# MCU.net
KiCad netlist of a schematic drawn in Altium Designer
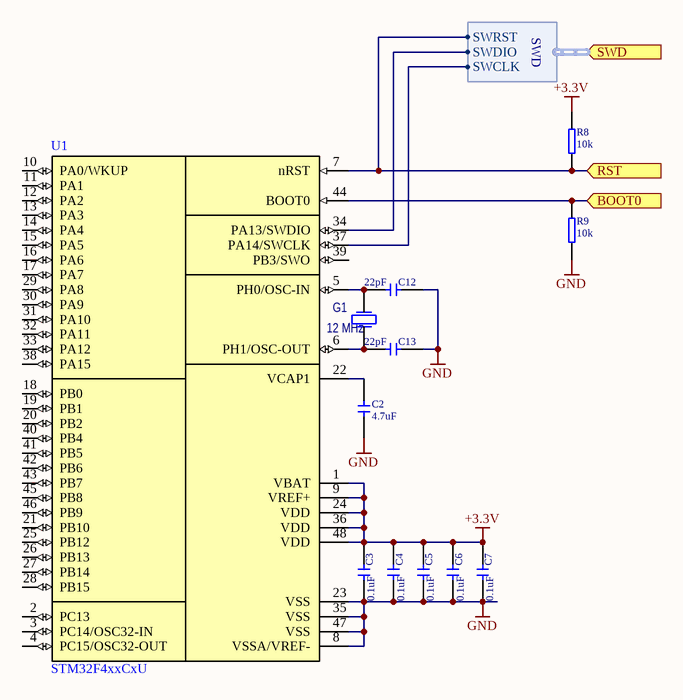
[diagram p0: MCU.SchDoc]

(export (version "E")
  (design (tool "Eeschema 10.0.6"))
  (components
    (comp (ref "C2")
      (value "4.7uF")
      (footprint "CERCAP 0603")
      (description "Capacitor")
      (fields (field (name "Comment") "CERCAP 0603 4.7uF * X7R"))
      (libsource (lib "!main") (part "!Capacitor"))
    )
    (comp (ref "C3")
      (value "0.1uF")
      (footprint "CERCAP 0402")
      (description "Capacitor")
      (fields (field (name "Comment") "CERCAP 0402 0.1uF * X7R"))
      (libsource (lib "!main") (part "!Capacitor"))
    )
    (comp (ref "C4")
      (value "0.1uF")
      (footprint "CERCAP 0402")
      (description "Capacitor")
      (fields (field (name "Comment") "CERCAP 0402 0.1uF * X7R"))
      (libsource (lib "!main") (part "!Capacitor"))
    )
    (comp (ref "C5")
      (value "0.1uF")
      (footprint "CERCAP 0402")
      (description "Capacitor")
      (fields (field (name "Comment") "CERCAP 0402 0.1uF * X7R"))
      (libsource (lib "!main") (part "!Capacitor"))
    )
    (comp (ref "C6")
      (value "0.1uF")
      (footprint "CERCAP 0402")
      (description "Capacitor")
      (fields (field (name "Comment") "CERCAP 0402 0.1uF * X7R"))
      (libsource (lib "!main") (part "!Capacitor"))
    )
    (comp (ref "C7")
      (value "0.1uF")
      (footprint "CERCAP 0402")
      (description "Capacitor")
      (fields (field (name "Comment") "CERCAP 0402 0.1uF * X7R"))
      (libsource (lib "!main") (part "!Capacitor"))
    )
    (comp (ref "C12")
      (value "22pF")
      (footprint "CERCAP 0402")
      (description "Capacitor")
      (fields (field (name "Comment") "CERCAP 0402 22pF * X7R"))
      (libsource (lib "!main") (part "!Capacitor"))
    )
    (comp (ref "C13")
      (value "22pF")
      (footprint "CERCAP 0402")
      (description "Capacitor")
      (fields (field (name "Comment") "CERCAP 0402 22pF * X7R"))
      (libsource (lib "!main") (part "!Capacitor"))
    )
    (comp (ref "G1")
      (value "12 MHz")
      (footprint "3225")
      (description "Crystal")
      (fields (field (name "Comment") "322512 MHz"))
      (libsource (lib "!main") (part "Crystal"))
    )
    (comp (ref "R8")
      (value "10k")
      (footprint "RES 0402")
      (description "Resistor")
      (fields (field (name "Comment") "RES 0402 10k"))
      (libsource (lib "!main") (part "!Resistor"))
    )
    (comp (ref "R9")
      (value "10k")
      (footprint "RES 0402")
      (description "Resistor")
      (fields (field (name "Comment") "RES 0402 10k"))
      (libsource (lib "!main") (part "!Resistor"))
    )
    (comp (ref "U1")
      (value "STM32F4xxCxU")
      (footprint "QFN-48")
      (description "Cortex-M4")
      (libsource (lib "MCU_CPU") (part "STM32F4xxCxU"))
    )
  )
  (nets
    (net (code "2") (name "+3.3V") (class "Default")
      (node (ref "C3") (pin "2") (pintype "passive"))
      (node (ref "C4") (pin "2") (pintype "passive"))
      (node (ref "C5") (pin "2") (pintype "passive"))
      (node (ref "C6") (pin "2") (pintype "passive"))
      (node (ref "C7") (pin "2") (pintype "passive"))
      (node (ref "R8") (pin "2") (pinfunction "12_2") (pintype "passive"))
      (node (ref "U1") (pin "1") (pinfunction "VBAT_1") (pintype "power_in"))
      (node (ref "U1") (pin "24") (pinfunction "VDD_24") (pintype "power_in"))
      (node (ref "U1") (pin "36") (pinfunction "VDD_36") (pintype "power_in"))
      (node (ref "U1") (pin "48") (pinfunction "VDD_48") (pintype "power_in"))
      (node (ref "U1") (pin "9") (pinfunction "VREF+_9") (pintype "power_in"))
    )
    (net (code "3") (name "/BOOT0") (class "Default")
      (node (ref "R9") (pin "2") (pinfunction "12_2") (pintype "passive"))
      (node (ref "U1") (pin "44") (pinfunction "BOOT0_44") (pintype "input"))
    )
    (net (code "4") (name "/RST") (class "Default")
      (node (ref "R8") (pin "1") (pinfunction "11_1") (pintype "passive"))
      (node (ref "U1") (pin "7") (pinfunction "nRST_7") (pintype "input"))
    )
    (net (code "5") (name "/SWCLK") (class "Default")
      (node (ref "U1") (pin "37") (pinfunction "PA14/SWCLK_37") (pintype "bidirectional"))
    )
    (net (code "6") (name "/SWDIO") (class "Default")
      (node (ref "U1") (pin "34") (pinfunction "PA13/SWDIO_34") (pintype "bidirectional"))
    )
    (net (code "8") (name "GND") (class "Default")
      (node (ref "C12") (pin "2") (pintype "passive"))
      (node (ref "C13") (pin "2") (pintype "passive"))
      (node (ref "C2") (pin "1") (pintype "passive"))
      (node (ref "C3") (pin "1") (pintype "passive"))
      (node (ref "C4") (pin "1") (pintype "passive"))
      (node (ref "C5") (pin "1") (pintype "passive"))
      (node (ref "C6") (pin "1") (pintype "passive"))
      (node (ref "C7") (pin "1") (pintype "passive"))
      (node (ref "R9") (pin "1") (pinfunction "11_1") (pintype "passive"))
      (node (ref "U1") (pin "23") (pinfunction "VSS_23") (pintype "power_in"))
      (node (ref "U1") (pin "35") (pinfunction "VSS_35") (pintype "power_in"))
      (node (ref "U1") (pin "47") (pinfunction "VSS_47") (pintype "power_in"))
      (node (ref "U1") (pin "8") (pinfunction "VSSA/VREF-_8") (pintype "power_in"))
    )
    (net (code "9") (name "Net-(U1-PH0{slash}OSC-IN)") (class "Default")
      (node (ref "C12") (pin "1") (pintype "passive"))
      (node (ref "G1") (pin "2") (pintype "passive"))
      (node (ref "U1") (pin "5") (pinfunction "PH0/OSC-IN_5") (pintype "bidirectional"))
    )
    (net (code "10") (name "Net-(U1-PH1{slash}OSC-OUT)") (class "Default")
      (node (ref "C13") (pin "1") (pintype "passive"))
      (node (ref "G1") (pin "1") (pintype "passive"))
      (node (ref "U1") (pin "6") (pinfunction "PH1/OSC-OUT_6") (pintype "bidirectional"))
    )
    (net (code "11") (name "Net-(U1-VCAP1)") (class "Default")
      (node (ref "C2") (pin "2") (pintype "passive"))
      (node (ref "U1") (pin "22") (pinfunction "VCAP1_22") (pintype "power_in"))
    )
    (net (code "12") (name "unconnected-(U1-PA0{slash}WKUP-Pad10)") (class "Default")
      (node (ref "U1") (pin "10") (pinfunction "PA0/WKUP_10") (pintype "bidirectional"))
    )
    (net (code "13") (name "unconnected-(U1-PA1-Pad11)") (class "Default")
      (node (ref "U1") (pin "11") (pinfunction "PA1_11") (pintype "bidirectional"))
    )
    (net (code "14") (name "unconnected-(U1-PA2-Pad12)") (class "Default")
      (node (ref "U1") (pin "12") (pinfunction "PA2_12") (pintype "bidirectional"))
    )
    (net (code "15") (name "unconnected-(U1-PA3-Pad13)") (class "Default")
      (node (ref "U1") (pin "13") (pinfunction "PA3_13") (pintype "bidirectional"))
    )
    (net (code "16") (name "unconnected-(U1-PA4-Pad14)") (class "Default")
      (node (ref "U1") (pin "14") (pinfunction "PA4_14") (pintype "bidirectional"))
    )
    (net (code "17") (name "unconnected-(U1-PA5-Pad15)") (class "Default")
      (node (ref "U1") (pin "15") (pinfunction "PA5_15") (pintype "bidirectional"))
    )
    (net (code "18") (name "unconnected-(U1-PA6-Pad16)") (class "Default")
      (node (ref "U1") (pin "16") (pinfunction "PA6_16") (pintype "bidirectional"))
    )
    (net (code "19") (name "unconnected-(U1-PA7-Pad17)") (class "Default")
      (node (ref "U1") (pin "17") (pinfunction "PA7_17") (pintype "bidirectional"))
    )
    (net (code "20") (name "unconnected-(U1-PA8-Pad29)") (class "Default")
      (node (ref "U1") (pin "29") (pinfunction "PA8_29") (pintype "bidirectional"))
    )
    (net (code "21") (name "unconnected-(U1-PA9-Pad30)") (class "Default")
      (node (ref "U1") (pin "30") (pinfunction "PA9_30") (pintype "bidirectional"))
    )
    (net (code "22") (name "unconnected-(U1-PA10-Pad31)") (class "Default")
      (node (ref "U1") (pin "31") (pinfunction "PA10_31") (pintype "bidirectional"))
    )
    (net (code "23") (name "unconnected-(U1-PA11-Pad32)") (class "Default")
      (node (ref "U1") (pin "32") (pinfunction "PA11_32") (pintype "bidirectional"))
    )
    (net (code "24") (name "unconnected-(U1-PA12-Pad33)") (class "Default")
      (node (ref "U1") (pin "33") (pinfunction "PA12_33") (pintype "bidirectional"))
    )
    (net (code "25") (name "unconnected-(U1-PA15-Pad38)") (class "Default")
      (node (ref "U1") (pin "38") (pinfunction "PA15_38") (pintype "bidirectional"))
    )
    (net (code "26") (name "unconnected-(U1-PB0-Pad18)") (class "Default")
      (node (ref "U1") (pin "18") (pinfunction "PB0_18") (pintype "bidirectional"))
    )
    (net (code "27") (name "unconnected-(U1-PB1-Pad19)") (class "Default")
      (node (ref "U1") (pin "19") (pinfunction "PB1_19") (pintype "bidirectional"))
    )
    (net (code "28") (name "unconnected-(U1-PB2-Pad20)") (class "Default")
      (node (ref "U1") (pin "20") (pinfunction "PB2_20") (pintype "bidirectional"))
    )
    (net (code "29") (name "unconnected-(U1-PB3{slash}SWO-Pad39)") (class "Default")
      (node (ref "U1") (pin "39") (pinfunction "PB3/SWO_39") (pintype "bidirectional"))
    )
    (net (code "30") (name "unconnected-(U1-PB4-Pad40)") (class "Default")
      (node (ref "U1") (pin "40") (pinfunction "PB4_40") (pintype "bidirectional"))
    )
    (net (code "31") (name "unconnected-(U1-PB5-Pad41)") (class "Default")
      (node (ref "U1") (pin "41") (pinfunction "PB5_41") (pintype "bidirectional"))
    )
    (net (code "32") (name "unconnected-(U1-PB6-Pad42)") (class "Default")
      (node (ref "U1") (pin "42") (pinfunction "PB6_42") (pintype "bidirectional"))
    )
    (net (code "33") (name "unconnected-(U1-PB7-Pad43)") (class "Default")
      (node (ref "U1") (pin "43") (pinfunction "PB7_43") (pintype "bidirectional"))
    )
    (net (code "34") (name "unconnected-(U1-PB8-Pad45)") (class "Default")
      (node (ref "U1") (pin "45") (pinfunction "PB8_45") (pintype "bidirectional"))
    )
    (net (code "35") (name "unconnected-(U1-PB9-Pad46)") (class "Default")
      (node (ref "U1") (pin "46") (pinfunction "PB9_46") (pintype "bidirectional"))
    )
    (net (code "36") (name "unconnected-(U1-PB10-Pad21)") (class "Default")
      (node (ref "U1") (pin "21") (pinfunction "PB10_21") (pintype "bidirectional"))
    )
    (net (code "37") (name "unconnected-(U1-PB12-Pad25)") (class "Default")
      (node (ref "U1") (pin "25") (pinfunction "PB12_25") (pintype "bidirectional"))
    )
    (net (code "38") (name "unconnected-(U1-PB13-Pad26)") (class "Default")
      (node (ref "U1") (pin "26") (pinfunction "PB13_26") (pintype "bidirectional"))
    )
    (net (code "39") (name "unconnected-(U1-PB14-Pad27)") (class "Default")
      (node (ref "U1") (pin "27") (pinfunction "PB14_27") (pintype "bidirectional"))
    )
    (net (code "40") (name "unconnected-(U1-PB15-Pad28)") (class "Default")
      (node (ref "U1") (pin "28") (pinfunction "PB15_28") (pintype "bidirectional"))
    )
    (net (code "41") (name "unconnected-(U1-PC13-Pad2)") (class "Default")
      (node (ref "U1") (pin "2") (pinfunction "PC13_2") (pintype "bidirectional"))
    )
    (net (code "42") (name "unconnected-(U1-PC14{slash}OSC32-IN-Pad3)") (class "Default")
      (node (ref "U1") (pin "3") (pinfunction "PC14/OSC32-IN_3") (pintype "bidirectional"))
    )
    (net (code "43") (name "unconnected-(U1-PC15{slash}OSC32-OUT-Pad4)") (class "Default")
      (node (ref "U1") (pin "4") (pinfunction "PC15/OSC32-OUT_4") (pintype "bidirectional"))
    )
  )
)
